# untitled.net
KiCad netlist of a schematic drawn in EAGLE
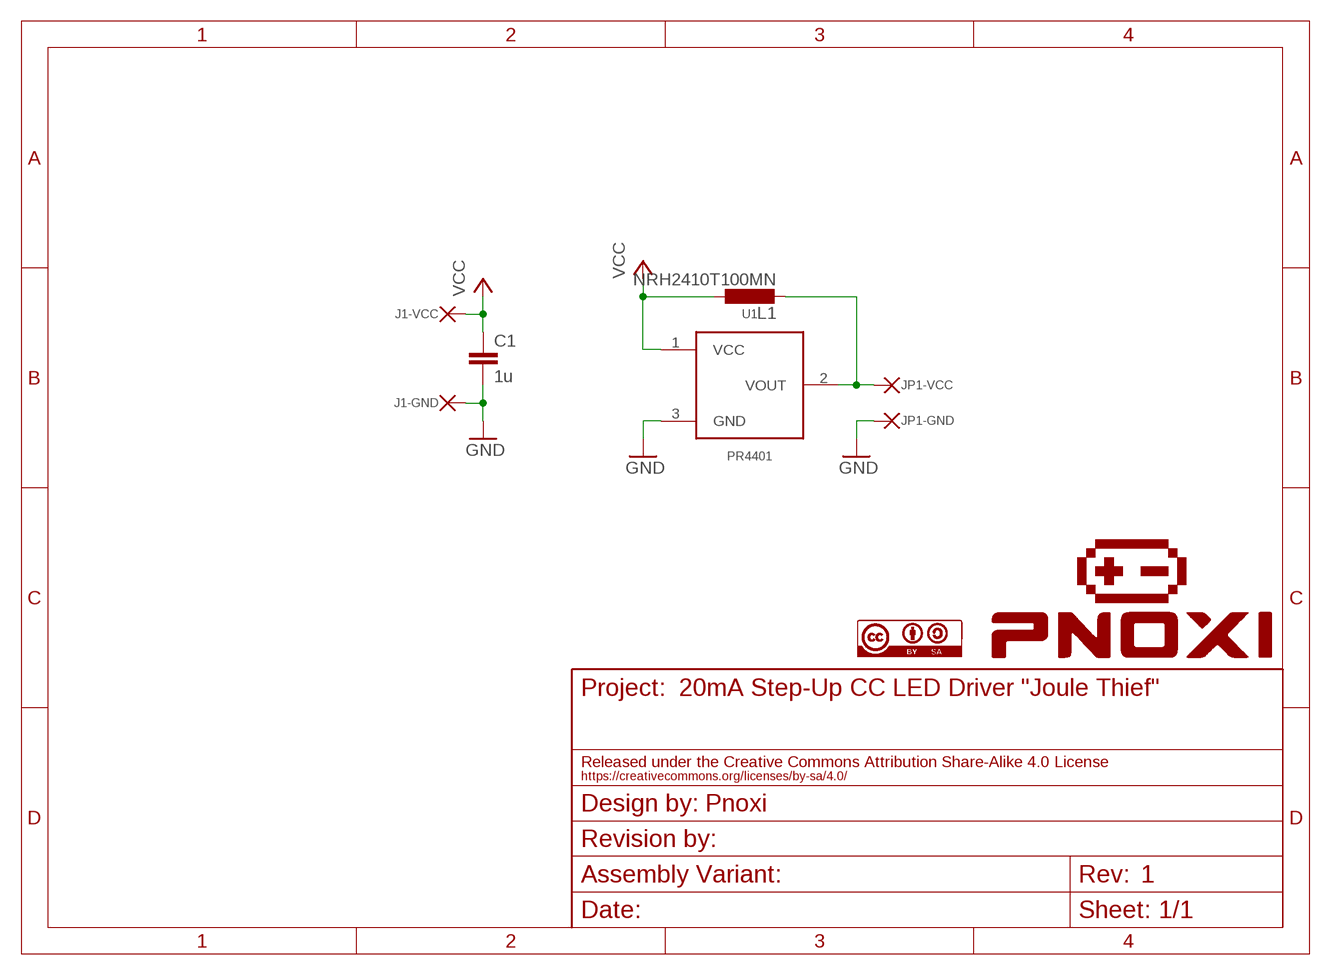
[diagram p0: schematic, sheet 1]

(export (version "E")
  (design (tool "Eeschema 10.0.6"))
  (components
    (comp (ref "C1")
      (value "1u")
      (footprint "eagle-import:0603")
      (libsource (lib "eagle-import") (part "C_EU_0603"))
    )
    (comp (ref "J1")
      (value "SMD_PAD2")
      (footprint "eagle-import:SMD_PAD_2")
      (libsource (lib "eagle-import") (part "SMD_PAD2"))
    )
    (comp (ref "JP1")
      (value "SMD_PAD2")
      (footprint "eagle-import:SMD_PAD_2")
      (libsource (lib "eagle-import") (part "SMD_PAD2"))
    )
    (comp (ref "L1")
      (value "NRH2410T100MN")
      (footprint "eagle-import:WALSIN_2.4X2.4X1MM")
      (libsource (lib "eagle-import") (part "L_EU_WALSIN_2.4X2.4X1MM"))
    )
    (comp (ref "U1")
      (value "PR4401")
      (footprint "eagle-import:SOT23-3")
      (libsource (lib "eagle-import") (part "ZXSC380FHTA"))
    )
  )
  (nets
    (net (code "1") (name "GND") (class "Default")
      (node (ref "C1") (pin "2") (pinfunction "2_2") (pintype "passive"))
      (node (ref "J1") (pin "GND") (pinfunction "P_GND") (pintype "passive"))
      (node (ref "J1") (pin "GND1") (pinfunction "P_GND1") (pintype "passive"))
      (node (ref "J1") (pin "GND2") (pinfunction "P_GND2") (pintype "passive"))
      (node (ref "J1") (pin "GND3") (pinfunction "P_GND3") (pintype "passive"))
      (node (ref "JP1") (pin "GND") (pinfunction "P_GND") (pintype "passive"))
      (node (ref "JP1") (pin "GND1") (pinfunction "P_GND1") (pintype "passive"))
      (node (ref "JP1") (pin "GND2") (pinfunction "P_GND2") (pintype "passive"))
      (node (ref "JP1") (pin "GND3") (pinfunction "P_GND3") (pintype "passive"))
      (node (ref "U1") (pin "3") (pinfunction "GND_3") (pintype "passive"))
    )
    (net (code "2") (name "Net-(L1-2)") (class "Default")
      (node (ref "JP1") (pin "VCC") (pinfunction "P_VCC") (pintype "passive"))
      (node (ref "JP1") (pin "VCC1") (pinfunction "P_VCC1") (pintype "passive"))
      (node (ref "JP1") (pin "VCC2") (pinfunction "P_VCC2") (pintype "passive"))
      (node (ref "JP1") (pin "VCC3") (pinfunction "P_VCC3") (pintype "passive"))
      (node (ref "L1") (pin "P$2") (pinfunction "2_P$2") (pintype "passive"))
      (node (ref "U1") (pin "2") (pinfunction "VOUT_2") (pintype "passive"))
    )
    (net (code "3") (name "VCC") (class "Default")
      (node (ref "C1") (pin "1") (pinfunction "1_1") (pintype "passive"))
      (node (ref "J1") (pin "VCC") (pinfunction "P_VCC") (pintype "passive"))
      (node (ref "J1") (pin "VCC1") (pinfunction "P_VCC1") (pintype "passive"))
      (node (ref "J1") (pin "VCC2") (pinfunction "P_VCC2") (pintype "passive"))
      (node (ref "J1") (pin "VCC3") (pinfunction "P_VCC3") (pintype "passive"))
      (node (ref "L1") (pin "P$1") (pinfunction "1_P$1") (pintype "passive"))
      (node (ref "U1") (pin "1") (pinfunction "VCC_1") (pintype "passive"))
    )
  )
)
